# ExportPinos.net
KiCad netlist of a schematic drawn in Altium Designer
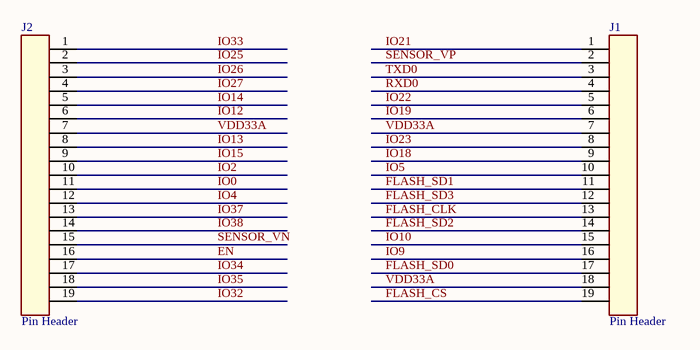
[diagram p0: ExportPinos.SchDoc]

(export (version "E")
  (design (tool "Eeschema 10.0.6"))
  (components
    (comp (ref "J1")
      (value "Pin Header")
      (footprint "Pin Header 19 Ways")
      (description "Connector Header PTH 0.100\" (2.54mm)")
      (libsource (lib "Connectors") (part "Pin Header 19 ways"))
    )
    (comp (ref "J2")
      (value "Pin Header")
      (footprint "Pin Header 19 Ways")
      (description "Connector Header PTH 0.100\" (2.54mm)")
      (libsource (lib "") (part "Pin Header 19 ways_1"))
    )
  )
  (nets
    (net (code "1") (name "/EN") (class "Default")
      (node (ref "J2") (pin "16") (pinfunction "16_16") (pintype "passive"))
    )
    (net (code "2") (name "/FLASH_CLK") (class "Default")
      (node (ref "J1") (pin "13") (pinfunction "13_13") (pintype "passive"))
    )
    (net (code "3") (name "/FLASH_CS") (class "Default")
      (node (ref "J1") (pin "19") (pinfunction "19_19") (pintype "passive"))
    )
    (net (code "4") (name "/FLASH_SD0") (class "Default")
      (node (ref "J1") (pin "17") (pinfunction "17_17") (pintype "passive"))
    )
    (net (code "5") (name "/FLASH_SD1") (class "Default")
      (node (ref "J1") (pin "11") (pinfunction "11_11") (pintype "passive"))
    )
    (net (code "6") (name "/FLASH_SD2") (class "Default")
      (node (ref "J1") (pin "14") (pinfunction "14_14") (pintype "passive"))
    )
    (net (code "7") (name "/FLASH_SD3") (class "Default")
      (node (ref "J1") (pin "12") (pinfunction "12_12") (pintype "passive"))
    )
    (net (code "8") (name "/IO0") (class "Default")
      (node (ref "J2") (pin "11") (pinfunction "11_11") (pintype "passive"))
    )
    (net (code "9") (name "/IO2") (class "Default")
      (node (ref "J2") (pin "10") (pinfunction "10_10") (pintype "passive"))
    )
    (net (code "10") (name "/IO4") (class "Default")
      (node (ref "J2") (pin "12") (pinfunction "12_12") (pintype "passive"))
    )
    (net (code "11") (name "/IO5") (class "Default")
      (node (ref "J1") (pin "10") (pinfunction "10_10") (pintype "passive"))
    )
    (net (code "12") (name "/IO9") (class "Default")
      (node (ref "J1") (pin "16") (pinfunction "16_16") (pintype "passive"))
    )
    (net (code "13") (name "/IO10") (class "Default")
      (node (ref "J1") (pin "15") (pinfunction "15_15") (pintype "passive"))
    )
    (net (code "14") (name "/IO12") (class "Default")
      (node (ref "J2") (pin "6") (pinfunction "6_6") (pintype "passive"))
    )
    (net (code "15") (name "/IO13") (class "Default")
      (node (ref "J2") (pin "8") (pinfunction "8_8") (pintype "passive"))
    )
    (net (code "16") (name "/IO14") (class "Default")
      (node (ref "J2") (pin "5") (pinfunction "5_5") (pintype "passive"))
    )
    (net (code "17") (name "/IO15") (class "Default")
      (node (ref "J2") (pin "9") (pinfunction "9_9") (pintype "passive"))
    )
    (net (code "18") (name "/IO18") (class "Default")
      (node (ref "J1") (pin "9") (pinfunction "9_9") (pintype "passive"))
    )
    (net (code "19") (name "/IO19") (class "Default")
      (node (ref "J1") (pin "6") (pinfunction "6_6") (pintype "passive"))
    )
    (net (code "20") (name "/IO21") (class "Default")
      (node (ref "J1") (pin "1") (pinfunction "1_1") (pintype "passive"))
    )
    (net (code "21") (name "/IO22") (class "Default")
      (node (ref "J1") (pin "5") (pinfunction "5_5") (pintype "passive"))
    )
    (net (code "22") (name "/IO23") (class "Default")
      (node (ref "J1") (pin "8") (pinfunction "8_8") (pintype "passive"))
    )
    (net (code "23") (name "/IO25") (class "Default")
      (node (ref "J2") (pin "2") (pinfunction "2_2") (pintype "passive"))
    )
    (net (code "24") (name "/IO26") (class "Default")
      (node (ref "J2") (pin "3") (pinfunction "3_3") (pintype "passive"))
    )
    (net (code "25") (name "/IO27") (class "Default")
      (node (ref "J2") (pin "4") (pinfunction "4_4") (pintype "passive"))
    )
    (net (code "26") (name "/IO32") (class "Default")
      (node (ref "J2") (pin "19") (pinfunction "19_19") (pintype "passive"))
    )
    (net (code "27") (name "/IO33") (class "Default")
      (node (ref "J2") (pin "1") (pinfunction "1_1") (pintype "passive"))
    )
    (net (code "28") (name "/IO34") (class "Default")
      (node (ref "J2") (pin "17") (pinfunction "17_17") (pintype "passive"))
    )
    (net (code "29") (name "/IO35") (class "Default")
      (node (ref "J2") (pin "18") (pinfunction "18_18") (pintype "passive"))
    )
    (net (code "30") (name "/IO37") (class "Default")
      (node (ref "J2") (pin "13") (pinfunction "13_13") (pintype "passive"))
    )
    (net (code "31") (name "/IO38") (class "Default")
      (node (ref "J2") (pin "14") (pinfunction "14_14") (pintype "passive"))
    )
    (net (code "32") (name "/RXD0") (class "Default")
      (node (ref "J1") (pin "4") (pinfunction "4_4") (pintype "passive"))
    )
    (net (code "33") (name "/SENSOR_VN") (class "Default")
      (node (ref "J2") (pin "15") (pinfunction "15_15") (pintype "passive"))
    )
    (net (code "34") (name "/SENSOR_VP") (class "Default")
      (node (ref "J1") (pin "2") (pinfunction "2_2") (pintype "passive"))
    )
    (net (code "35") (name "/TXD0") (class "Default")
      (node (ref "J1") (pin "3") (pinfunction "3_3") (pintype "passive"))
    )
    (net (code "36") (name "/VDD33A") (class "Default")
      (node (ref "J1") (pin "18") (pinfunction "18_18") (pintype "passive"))
      (node (ref "J1") (pin "7") (pinfunction "7_7") (pintype "passive"))
      (node (ref "J2") (pin "7") (pinfunction "7_7") (pintype "passive"))
    )
  )
)
